# line_follower.net
KiCad netlist of a schematic drawn in Altium Designer
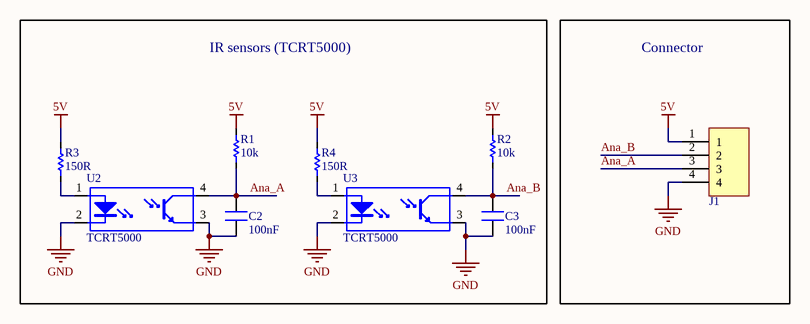
[diagram p0: line_follower.SchDoc]

(export (version "E")
  (design (tool "Eeschema 10.0.6"))
  (components
    (comp (ref "C2")
      (value "100nF")
      (footprint "C0603")
      (description "Ceramic Capacitor SMD")
      (fields (field (name "Comment") "C"))
      (libsource (lib "Main") (part "C"))
    )
    (comp (ref "C3")
      (value "100nF")
      (footprint "C0603")
      (description "Ceramic Capacitor SMD")
      (fields (field (name "Comment") "C"))
      (libsource (lib "Main") (part "C"))
    )
    (comp (ref "J1")
      (value "CONN_4P")
      (footprint "JST B4B-PH-K-S")
      (description "Connector, 4P")
      (libsource (lib "Main") (part "CONN_4P"))
    )
    (comp (ref "R1")
      (value "10k")
      (footprint "R0603")
      (description "Resistor SMD")
      (fields (field (name "Comment") "R"))
      (libsource (lib "Main") (part "R"))
    )
    (comp (ref "R2")
      (value "10k")
      (footprint "R0603")
      (description "Resistor SMD")
      (fields (field (name "Comment") "R"))
      (libsource (lib "Main") (part "R"))
    )
    (comp (ref "R3")
      (value "150R")
      (footprint "R0603")
      (description "Resistor SMD")
      (fields (field (name "Comment") "R"))
      (libsource (lib "Main") (part "R"))
    )
    (comp (ref "R4")
      (value "150R")
      (footprint "R0603")
      (description "Resistor SMD")
      (fields (field (name "Comment") "R"))
      (libsource (lib "Main") (part "R"))
    )
    (comp (ref "U2")
      (value "TCRT5000")
      (footprint "TCRT5000")
      (description "Reflective Optical Sensor with Transistor Output")
      (libsource (lib "Main") (part "TCRT5000"))
    )
    (comp (ref "U3")
      (value "TCRT5000")
      (footprint "TCRT5000")
      (description "Reflective Optical Sensor with Transistor Output")
      (libsource (lib "Main") (part "TCRT5000"))
    )
  )
  (nets
    (net (code "1") (name "/Ana_A") (class "Default")
      (node (ref "C2") (pin "2") (pintype "passive"))
      (node (ref "J1") (pin "3") (pinfunction "3_3") (pintype "passive"))
      (node (ref "R1") (pin "1") (pinfunction "1_1") (pintype "passive"))
      (node (ref "U2") (pin "4") (pinfunction "C_4") (pintype "passive"))
    )
    (net (code "2") (name "/Ana_B") (class "Default")
      (node (ref "C3") (pin "2") (pintype "passive"))
      (node (ref "J1") (pin "2") (pinfunction "2_2") (pintype "passive"))
      (node (ref "R2") (pin "1") (pinfunction "1_1") (pintype "passive"))
      (node (ref "U3") (pin "4") (pinfunction "C_4") (pintype "passive"))
    )
    (net (code "3") (name "5V") (class "Default")
      (node (ref "J1") (pin "1") (pinfunction "1_1") (pintype "passive"))
      (node (ref "R1") (pin "2") (pinfunction "2_2") (pintype "passive"))
      (node (ref "R2") (pin "2") (pinfunction "2_2") (pintype "passive"))
      (node (ref "R3") (pin "2") (pinfunction "2_2") (pintype "passive"))
      (node (ref "R4") (pin "2") (pinfunction "2_2") (pintype "passive"))
    )
    (net (code "4") (name "GND") (class "Default")
      (node (ref "C2") (pin "1") (pintype "passive"))
      (node (ref "C3") (pin "1") (pintype "passive"))
      (node (ref "J1") (pin "4") (pinfunction "4_4") (pintype "passive"))
      (node (ref "U2") (pin "2") (pinfunction "K_2") (pintype "passive"))
      (node (ref "U2") (pin "3") (pinfunction "E_3") (pintype "passive"))
      (node (ref "U3") (pin "2") (pinfunction "K_2") (pintype "passive"))
      (node (ref "U3") (pin "3") (pinfunction "E_3") (pintype "passive"))
    )
    (net (code "5") (name "Net-(U2-A)") (class "Default")
      (node (ref "R3") (pin "1") (pinfunction "1_1") (pintype "passive"))
      (node (ref "U2") (pin "1") (pinfunction "A_1") (pintype "passive"))
    )
    (net (code "6") (name "Net-(U3-A)") (class "Default")
      (node (ref "R4") (pin "1") (pinfunction "1_1") (pintype "passive"))
      (node (ref "U3") (pin "1") (pinfunction "A_1") (pintype "passive"))
    )
  )
)
